# StepperLogic.net
KiCad netlist of a schematic drawn in Altium Designer
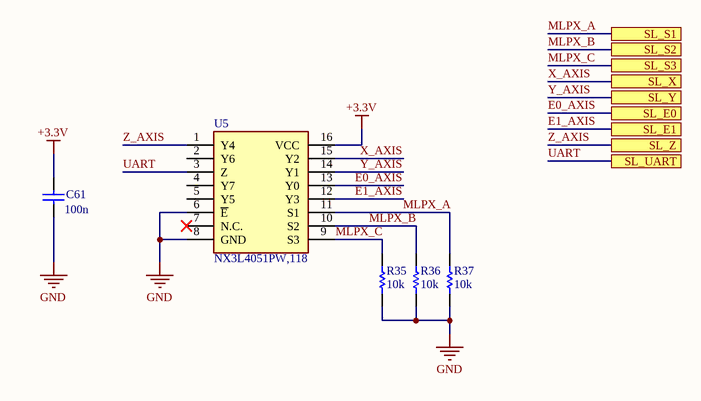
[diagram p0: StepperLogic.SchDoc]

(export (version "E")
  (design (tool "Eeschema 10.0.6"))
  (components
    (comp (ref "C61")
      (value "100n")
      (footprint "RAD-0.3")
      (description "Capacitor")
      (fields (field (name "Comment") "X5R") (field (name "PUBLISHER") "Altium Limited"))
      (libsource (lib "Miscellaneous Devices") (part "Cap"))
    )
    (comp (ref "R35")
      (value "10k")
      (footprint "AXIAL-0.3")
      (description "Resistor")
      (fields (field (name "Comment") "Res1") (field (name "PUBLISHER") "Altium Limited"))
      (libsource (lib "Miscellaneous Devices") (part "Res1"))
    )
    (comp (ref "R36")
      (value "10k")
      (footprint "AXIAL-0.3")
      (description "Resistor")
      (fields (field (name "Comment") "Res1") (field (name "PUBLISHER") "Altium Limited"))
      (libsource (lib "Miscellaneous Devices") (part "Res1"))
    )
    (comp (ref "R37")
      (value "10k")
      (footprint "AXIAL-0.3")
      (description "Resistor")
      (fields (field (name "Comment") "Res1") (field (name "PUBLISHER") "Altium Limited"))
      (libsource (lib "Miscellaneous Devices") (part "Res1"))
    )
    (comp (ref "U5")
      (value "NX3L4051PW,118")
      (footprint "SamacSys:SOP65P640X110-16N")
      (description "Integrated Circuit")
      (fields (field (name "MOUSER PART NUMBER") "771-NX3L4051PW118"))
      (libsource (lib "*") (part "NX3L4051PW,118"))
    )
  )
  (nets
    (net (code "1") (name "+3.3V") (class "Default")
      (node (ref "C61") (pin "1") (pinfunction "1_1") (pintype "passive"))
      (node (ref "U5") (pin "16") (pinfunction "VCC_16") (pintype "passive"))
    )
    (net (code "2") (name "/E0_AXIS") (class "Default")
      (node (ref "U5") (pin "13") (pinfunction "Y0_13") (pintype "passive"))
    )
    (net (code "3") (name "/E1_AXIS") (class "Default")
      (node (ref "U5") (pin "12") (pinfunction "Y3_12") (pintype "passive"))
    )
    (net (code "4") (name "/MLPX_A") (class "Default")
      (node (ref "R37") (pin "2") (pinfunction "2_2") (pintype "passive"))
      (node (ref "U5") (pin "11") (pinfunction "S1_11") (pintype "passive"))
    )
    (net (code "5") (name "/MLPX_B") (class "Default")
      (node (ref "R36") (pin "2") (pinfunction "2_2") (pintype "passive"))
      (node (ref "U5") (pin "10") (pinfunction "S2_10") (pintype "passive"))
    )
    (net (code "6") (name "/MLPX_C") (class "Default")
      (node (ref "R35") (pin "2") (pinfunction "2_2") (pintype "passive"))
      (node (ref "U5") (pin "9") (pinfunction "S3_9") (pintype "passive"))
    )
    (net (code "7") (name "/UART") (class "Default")
      (node (ref "U5") (pin "3") (pinfunction "Z_3") (pintype "passive"))
    )
    (net (code "8") (name "/X_AXIS") (class "Default")
      (node (ref "U5") (pin "15") (pinfunction "Y2_15") (pintype "passive"))
    )
    (net (code "9") (name "/Y_AXIS") (class "Default")
      (node (ref "U5") (pin "14") (pinfunction "Y1_14") (pintype "passive"))
    )
    (net (code "10") (name "/Z_AXIS") (class "Default")
      (node (ref "U5") (pin "1") (pinfunction "Y4_1") (pintype "passive"))
    )
    (net (code "11") (name "GND") (class "Default")
      (node (ref "C61") (pin "2") (pinfunction "2_2") (pintype "passive"))
      (node (ref "R35") (pin "1") (pinfunction "1_1") (pintype "passive"))
      (node (ref "R36") (pin "1") (pinfunction "1_1") (pintype "passive"))
      (node (ref "R37") (pin "1") (pinfunction "1_1") (pintype "passive"))
      (node (ref "U5") (pin "6") (pinfunction "~{E}_6") (pintype "passive"))
      (node (ref "U5") (pin "8") (pinfunction "GND_8") (pintype "passive"))
    )
    (net (code "12") (name "unconnected-(U5-N.C.-Pad7)") (class "Default")
      (node (ref "U5") (pin "7") (pinfunction "N.C._7") (pintype "passive+no_connect"))
    )
    (net (code "13") (name "unconnected-(U5-Y5-Pad5)") (class "Default")
      (node (ref "U5") (pin "5") (pinfunction "Y5_5") (pintype "passive"))
    )
    (net (code "14") (name "unconnected-(U5-Y6-Pad2)") (class "Default")
      (node (ref "U5") (pin "2") (pinfunction "Y6_2") (pintype "passive"))
    )
    (net (code "15") (name "unconnected-(U5-Y7-Pad4)") (class "Default")
      (node (ref "U5") (pin "4") (pinfunction "Y7_4") (pintype "passive"))
    )
  )
)
